# introAu.net
KiCad netlist of a schematic drawn in EAGLE
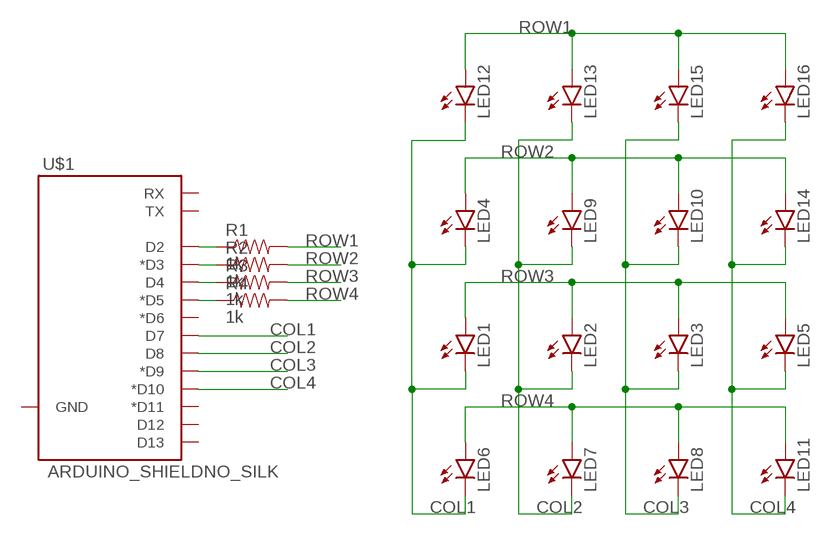
[diagram p0: schematic, sheet 1]

(export (version "E")
  (design (tool "Eeschema 10.0.6"))
  (components
    (comp (ref "LED1")
      (value "LED5MM")
      (footprint "eagle-import:LED5MM")
      (libsource (lib "eagle-import") (part "LED5MM"))
    )
    (comp (ref "LED2")
      (value "LED5MM")
      (footprint "eagle-import:LED5MM")
      (libsource (lib "eagle-import") (part "LED5MM"))
    )
    (comp (ref "LED3")
      (value "LED5MM")
      (footprint "eagle-import:LED5MM")
      (libsource (lib "eagle-import") (part "LED5MM"))
    )
    (comp (ref "LED4")
      (value "LED5MM")
      (footprint "eagle-import:LED5MM")
      (libsource (lib "eagle-import") (part "LED5MM"))
    )
    (comp (ref "LED5")
      (value "LED5MM")
      (footprint "eagle-import:LED5MM")
      (libsource (lib "eagle-import") (part "LED5MM"))
    )
    (comp (ref "LED6")
      (value "LED5MM")
      (footprint "eagle-import:LED5MM")
      (libsource (lib "eagle-import") (part "LED5MM"))
    )
    (comp (ref "LED7")
      (value "LED5MM")
      (footprint "eagle-import:LED5MM")
      (libsource (lib "eagle-import") (part "LED5MM"))
    )
    (comp (ref "LED8")
      (value "LED5MM")
      (footprint "eagle-import:LED5MM")
      (libsource (lib "eagle-import") (part "LED5MM"))
    )
    (comp (ref "LED9")
      (value "LED5MM")
      (footprint "eagle-import:LED5MM")
      (libsource (lib "eagle-import") (part "LED5MM"))
    )
    (comp (ref "LED10")
      (value "LED5MM")
      (footprint "eagle-import:LED5MM")
      (libsource (lib "eagle-import") (part "LED5MM"))
    )
    (comp (ref "LED11")
      (value "LED5MM")
      (footprint "eagle-import:LED5MM")
      (libsource (lib "eagle-import") (part "LED5MM"))
    )
    (comp (ref "LED12")
      (value "LED5MM")
      (footprint "eagle-import:LED5MM")
      (libsource (lib "eagle-import") (part "LED5MM"))
    )
    (comp (ref "LED13")
      (value "LED5MM")
      (footprint "eagle-import:LED5MM")
      (libsource (lib "eagle-import") (part "LED5MM"))
    )
    (comp (ref "LED14")
      (value "LED5MM")
      (footprint "eagle-import:LED5MM")
      (libsource (lib "eagle-import") (part "LED5MM"))
    )
    (comp (ref "LED15")
      (value "LED5MM")
      (footprint "eagle-import:LED5MM")
      (libsource (lib "eagle-import") (part "LED5MM"))
    )
    (comp (ref "LED16")
      (value "LED5MM")
      (footprint "eagle-import:LED5MM")
      (libsource (lib "eagle-import") (part "LED5MM"))
    )
    (comp (ref "R1")
      (value "1k")
      (footprint "eagle-import:AXIAL-0.3EZ")
      (libsource (lib "eagle-import") (part "1KOHM1/4W5%(PTH)HORIZ-KIT"))
    )
    (comp (ref "R2")
      (value "1k")
      (footprint "eagle-import:AXIAL-0.3EZ")
      (libsource (lib "eagle-import") (part "1KOHM1/4W5%(PTH)HORIZ-KIT"))
    )
    (comp (ref "R3")
      (value "1k")
      (footprint "eagle-import:AXIAL-0.3EZ")
      (libsource (lib "eagle-import") (part "1KOHM1/4W5%(PTH)HORIZ-KIT"))
    )
    (comp (ref "R4")
      (value "1k")
      (footprint "eagle-import:AXIAL-0.3EZ")
      (libsource (lib "eagle-import") (part "1KOHM1/4W5%(PTH)HORIZ-KIT"))
    )
    (comp (ref "U$1")
      (value "ARDUINO_SHIELDNO_SILK")
      (footprint "eagle-import:DUEMILANOVE_VIAS")
      (libsource (lib "eagle-import") (part "ARDUINO_SHIELDNO_SILK"))
    )
  )
  (nets
    (net (code "1") (name "/COL1") (class "Default")
      (node (ref "LED1") (pin "K") (pinfunction "C_K") (pintype "passive"))
      (node (ref "LED12") (pin "K") (pinfunction "C_K") (pintype "passive"))
      (node (ref "LED4") (pin "K") (pinfunction "C_K") (pintype "passive"))
      (node (ref "LED6") (pin "K") (pinfunction "C_K") (pintype "passive"))
      (node (ref "U$1") (pin "D7") (pinfunction "D7_D7") (pintype "bidirectional"))
    )
    (net (code "2") (name "/COL2") (class "Default")
      (node (ref "LED13") (pin "K") (pinfunction "C_K") (pintype "passive"))
      (node (ref "LED2") (pin "K") (pinfunction "C_K") (pintype "passive"))
      (node (ref "LED7") (pin "K") (pinfunction "C_K") (pintype "passive"))
      (node (ref "LED9") (pin "K") (pinfunction "C_K") (pintype "passive"))
      (node (ref "U$1") (pin "D8") (pinfunction "D8_D8") (pintype "bidirectional"))
    )
    (net (code "3") (name "/COL3") (class "Default")
      (node (ref "LED10") (pin "K") (pinfunction "C_K") (pintype "passive"))
      (node (ref "LED15") (pin "K") (pinfunction "C_K") (pintype "passive"))
      (node (ref "LED3") (pin "K") (pinfunction "C_K") (pintype "passive"))
      (node (ref "LED8") (pin "K") (pinfunction "C_K") (pintype "passive"))
      (node (ref "U$1") (pin "D9") (pinfunction "*D9_D9") (pintype "bidirectional"))
    )
    (net (code "4") (name "/COL4") (class "Default")
      (node (ref "LED11") (pin "K") (pinfunction "C_K") (pintype "passive"))
      (node (ref "LED14") (pin "K") (pinfunction "C_K") (pintype "passive"))
      (node (ref "LED16") (pin "K") (pinfunction "C_K") (pintype "passive"))
      (node (ref "LED5") (pin "K") (pinfunction "C_K") (pintype "passive"))
      (node (ref "U$1") (pin "D10") (pinfunction "*D10_D10") (pintype "bidirectional"))
    )
    (net (code "5") (name "/ROW1") (class "Default")
      (node (ref "LED12") (pin "A") (pinfunction "A_A") (pintype "passive"))
      (node (ref "LED13") (pin "A") (pinfunction "A_A") (pintype "passive"))
      (node (ref "LED15") (pin "A") (pinfunction "A_A") (pintype "passive"))
      (node (ref "LED16") (pin "A") (pinfunction "A_A") (pintype "passive"))
      (node (ref "R1") (pin "P$2") (pinfunction "2_P$2") (pintype "passive"))
    )
    (net (code "6") (name "/ROW2") (class "Default")
      (node (ref "LED10") (pin "A") (pinfunction "A_A") (pintype "passive"))
      (node (ref "LED14") (pin "A") (pinfunction "A_A") (pintype "passive"))
      (node (ref "LED4") (pin "A") (pinfunction "A_A") (pintype "passive"))
      (node (ref "LED9") (pin "A") (pinfunction "A_A") (pintype "passive"))
      (node (ref "R2") (pin "P$2") (pinfunction "2_P$2") (pintype "passive"))
    )
    (net (code "7") (name "/ROW3") (class "Default")
      (node (ref "LED1") (pin "A") (pinfunction "A_A") (pintype "passive"))
      (node (ref "LED2") (pin "A") (pinfunction "A_A") (pintype "passive"))
      (node (ref "LED3") (pin "A") (pinfunction "A_A") (pintype "passive"))
      (node (ref "LED5") (pin "A") (pinfunction "A_A") (pintype "passive"))
      (node (ref "R3") (pin "P$2") (pinfunction "2_P$2") (pintype "passive"))
    )
    (net (code "8") (name "/ROW4") (class "Default")
      (node (ref "LED11") (pin "A") (pinfunction "A_A") (pintype "passive"))
      (node (ref "LED6") (pin "A") (pinfunction "A_A") (pintype "passive"))
      (node (ref "LED7") (pin "A") (pinfunction "A_A") (pintype "passive"))
      (node (ref "LED8") (pin "A") (pinfunction "A_A") (pintype "passive"))
      (node (ref "R4") (pin "P$2") (pinfunction "2_P$2") (pintype "passive"))
    )
    (net (code "9") (name "Net-(R1-1)") (class "Default")
      (node (ref "R1") (pin "P$1") (pinfunction "1_P$1") (pintype "passive"))
      (node (ref "U$1") (pin "D2") (pinfunction "D2_D2") (pintype "bidirectional"))
    )
    (net (code "10") (name "Net-(R2-1)") (class "Default")
      (node (ref "R2") (pin "P$1") (pinfunction "1_P$1") (pintype "passive"))
      (node (ref "U$1") (pin "D3") (pinfunction "*D3_D3") (pintype "bidirectional"))
    )
    (net (code "11") (name "Net-(R3-1)") (class "Default")
      (node (ref "R3") (pin "P$1") (pinfunction "1_P$1") (pintype "passive"))
      (node (ref "U$1") (pin "D4") (pinfunction "D4_D4") (pintype "bidirectional"))
    )
    (net (code "12") (name "Net-(R4-1)") (class "Default")
      (node (ref "R4") (pin "P$1") (pinfunction "1_P$1") (pintype "passive"))
      (node (ref "U$1") (pin "D5") (pinfunction "*D5_D5") (pintype "bidirectional"))
    )
    (net (code "13") (name "unconnected-(U$1-*D6-PadD6)") (class "Default")
      (node (ref "U$1") (pin "D6") (pinfunction "*D6_D6") (pintype "bidirectional"))
    )
    (net (code "14") (name "unconnected-(U$1-*D11-PadD11)") (class "Default")
      (node (ref "U$1") (pin "D11") (pinfunction "*D11_D11") (pintype "bidirectional"))
    )
    (net (code "15") (name "unconnected-(U$1-GND-PadGND@2)") (class "Default")
      (node (ref "U$1") (pin "GND@2") (pinfunction "GND_GND@2") (pintype "bidirectional"))
    )
    (net (code "16") (name "unconnected-(U$1-PadD12)") (class "Default")
      (node (ref "U$1") (pin "D12") (pinfunction "D12_D12") (pintype "bidirectional"))
    )
    (net (code "17") (name "unconnected-(U$1-PadD13)") (class "Default")
      (node (ref "U$1") (pin "D13") (pinfunction "D13_D13") (pintype "bidirectional"))
    )
    (net (code "18") (name "unconnected-(U$1-PadRX)") (class "Default")
      (node (ref "U$1") (pin "RX") (pinfunction "RX_RX") (pintype "bidirectional"))
    )
    (net (code "19") (name "unconnected-(U$1-PadTX)") (class "Default")
      (node (ref "U$1") (pin "TX") (pinfunction "TX_TX") (pintype "bidirectional"))
    )
  )
)
